# Schematic_final.net
KiCad netlist of a schematic drawn in EAGLE
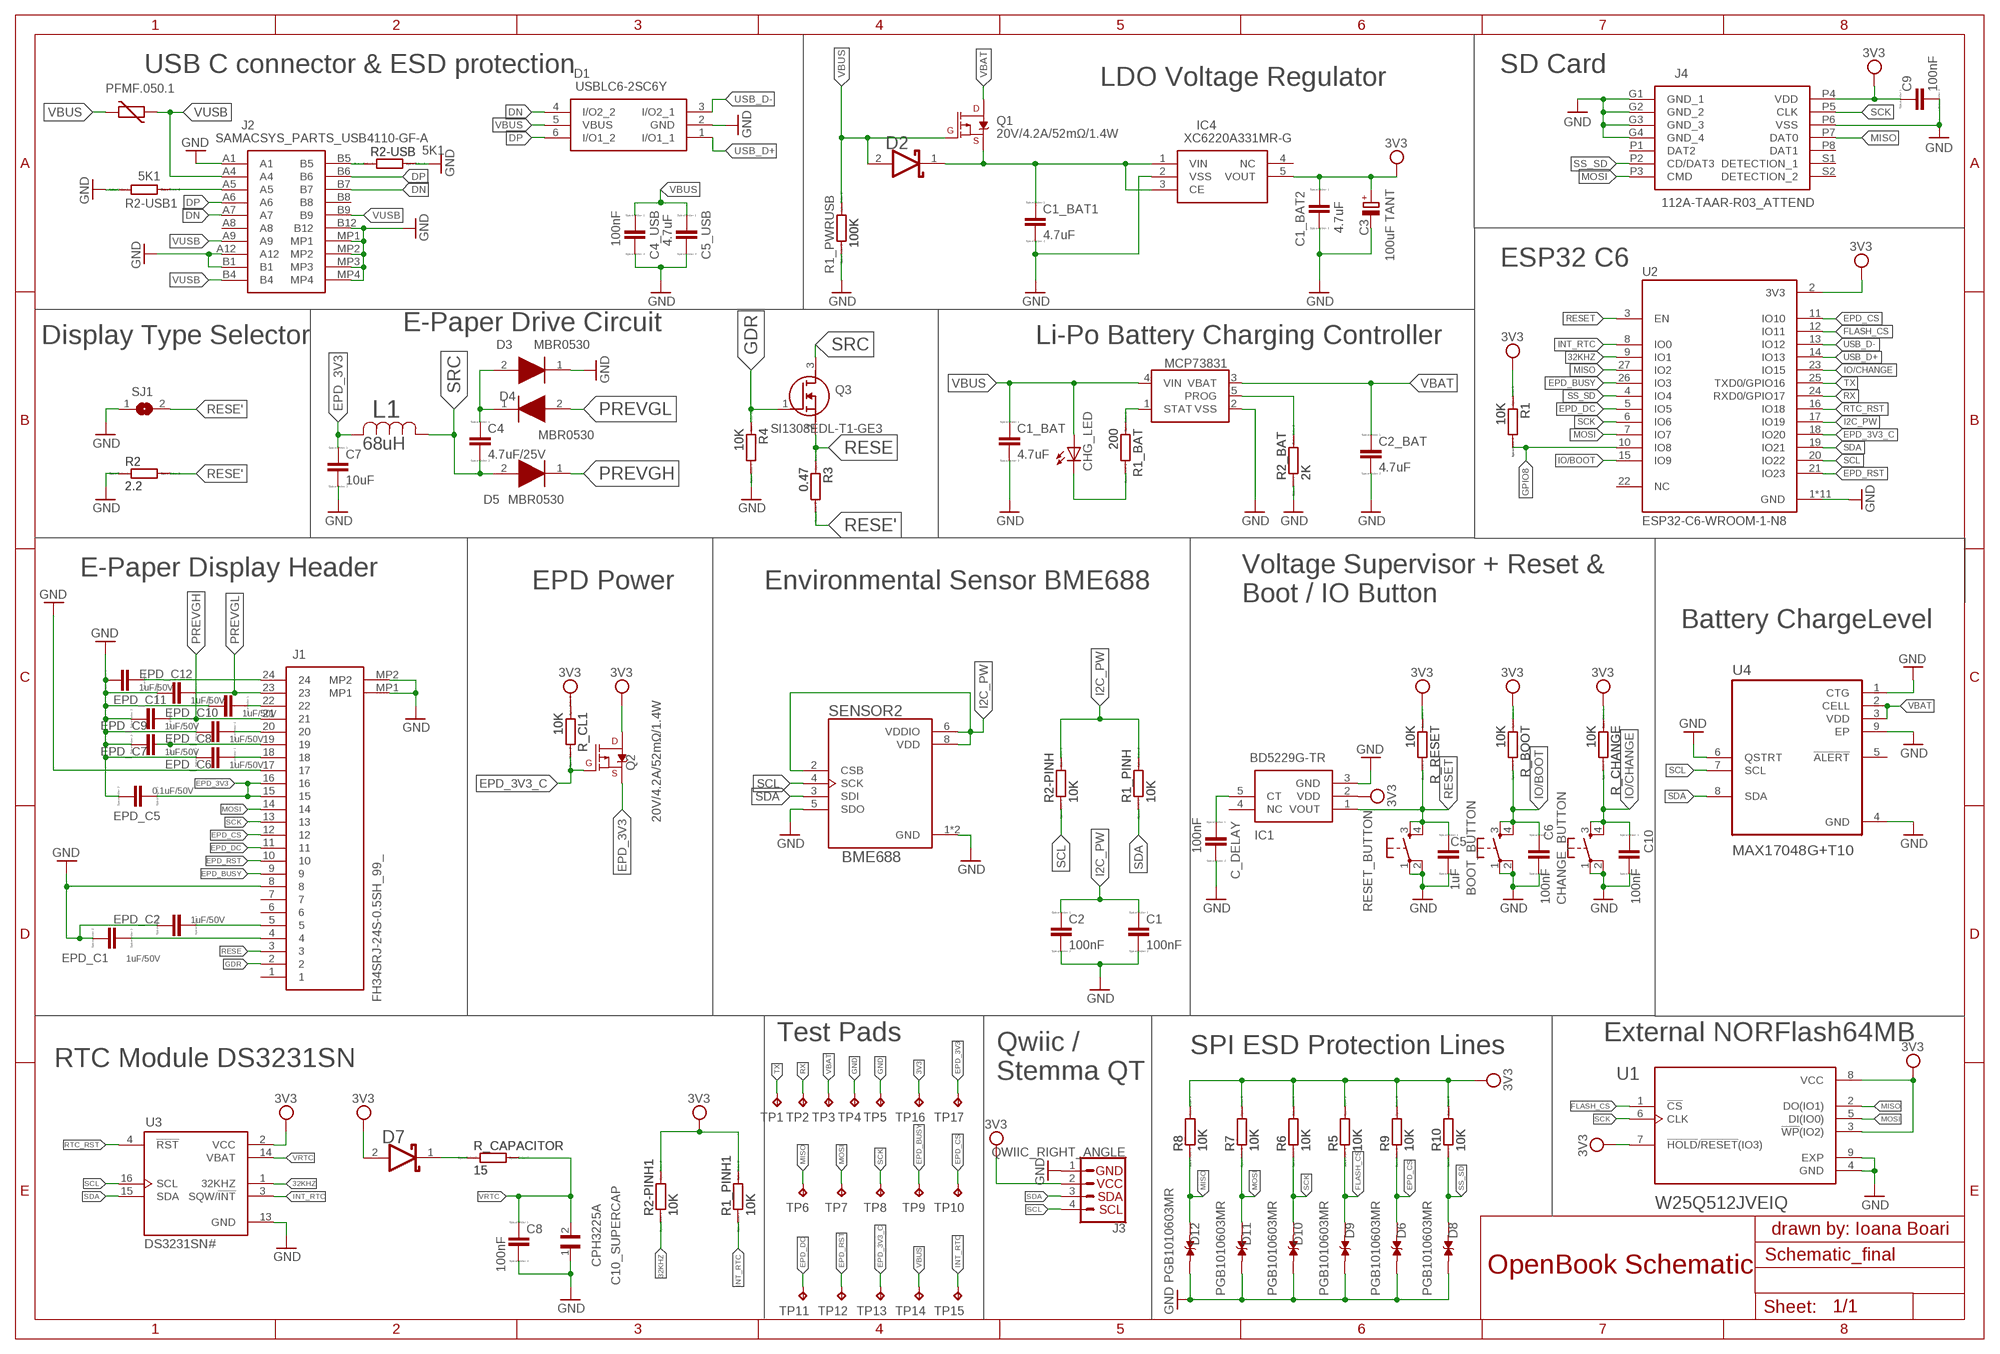
[diagram p0: schematic, sheet 1]

(export (version "E")
  (design (tool "Eeschema 10.0.6"))
  (components
    (comp (ref "BOOT_BUTTON")
      (value "BUTTON_CUSYOMV1")
      (footprint "eagle-import:MYBUTTON")
      (libsource (lib "eagle-import") (part "BUTTON_CUSYOMV1"))
    )
    (comp (ref "C1")
      (value "100nF")
      (footprint "eagle-import:ESP32_WROVER_EAGLE-LTSPICE_C0402")
      (libsource (lib "eagle-import") (part "ESP32_WROVER_EAGLE-LTSPICE_CC0402"))
    )
    (comp (ref "C1_BAT")
      (value "4.7uF")
      (footprint "eagle-import:ESP32_WROVER_EAGLE-LTSPICE_C0402")
      (libsource (lib "eagle-import") (part "ESP32_WROVER_EAGLE-LTSPICE_CC0402"))
    )
    (comp (ref "C1_BAT1")
      (value "4.7uF")
      (footprint "eagle-import:ESP32_WROVER_EAGLE-LTSPICE_C0402")
      (libsource (lib "eagle-import") (part "ESP32_WROVER_EAGLE-LTSPICE_CC0402"))
    )
    (comp (ref "C1_BAT2")
      (value "4.7uF")
      (footprint "eagle-import:EAGLE-LTSPICE_C0402")
      (libsource (lib "eagle-import") (part "EAGLE-LTSPICE_CC0402"))
    )
    (comp (ref "C2")
      (value "100nF")
      (footprint "eagle-import:ESP32_WROVER_EAGLE-LTSPICE_C0402")
      (libsource (lib "eagle-import") (part "ESP32_WROVER_EAGLE-LTSPICE_CC0402"))
    )
    (comp (ref "C2_BAT")
      (value "4.7uF")
      (footprint "eagle-import:ESP32_WROVER_EAGLE-LTSPICE_C0402")
      (libsource (lib "eagle-import") (part "ESP32_WROVER_EAGLE-LTSPICE_CC0402"))
    )
    (comp (ref "C3")
      (value "100uF TANT")
      (footprint "eagle-import:RCL_CT3528")
      (libsource (lib "eagle-import") (part "RCL_CPOL-EUCT3528"))
    )
    (comp (ref "C4")
      (value "4.7uF/25V")
      (footprint "eagle-import:ESP32_WROVER_EAGLE-LTSPICE_C0402")
      (libsource (lib "eagle-import") (part "ESP32_WROVER_EAGLE-LTSPICE_CC0402"))
    )
    (comp (ref "C4_USB")
      (value "100nF")
      (footprint "eagle-import:ESP32_WROVER_EAGLE-LTSPICE_C0402")
      (libsource (lib "eagle-import") (part "ESP32_WROVER_EAGLE-LTSPICE_CC0402"))
    )
    (comp (ref "C5")
      (value "1uF")
      (footprint "eagle-import:ESP32_WROVER_EAGLE-LTSPICE_C0402")
      (libsource (lib "eagle-import") (part "ESP32_WROVER_EAGLE-LTSPICE_CC0402"))
    )
    (comp (ref "C5_USB")
      (value "4.7uF")
      (footprint "eagle-import:ESP32_WROVER_EAGLE-LTSPICE_C0402")
      (libsource (lib "eagle-import") (part "ESP32_WROVER_EAGLE-LTSPICE_CC0402"))
    )
    (comp (ref "C6")
      (value "100nF")
      (footprint "eagle-import:ESP32_WROVER_EAGLE-LTSPICE_C0402")
      (libsource (lib "eagle-import") (part "ESP32_WROVER_EAGLE-LTSPICE_CC0402"))
    )
    (comp (ref "C7")
      (value "10uF")
      (footprint "eagle-import:ESP32_WROVER_EAGLE-LTSPICE_C0402")
      (libsource (lib "eagle-import") (part "ESP32_WROVER_EAGLE-LTSPICE_CC0402"))
    )
    (comp (ref "C8")
      (value "100nF")
      (footprint "eagle-import:ESP32_WROVER_EAGLE-LTSPICE_C0402")
      (libsource (lib "eagle-import") (part "ESP32_WROVER_EAGLE-LTSPICE_CC0402"))
    )
    (comp (ref "C9")
      (value "100nF")
      (footprint "eagle-import:ESP32_WROVER_EAGLE-LTSPICE_C0402")
      (libsource (lib "eagle-import") (part "ESP32_WROVER_EAGLE-LTSPICE_CC0402"))
    )
    (comp (ref "C10")
      (value "100nF")
      (footprint "eagle-import:ESP32_WROVER_EAGLE-LTSPICE_C0402")
      (libsource (lib "eagle-import") (part "ESP32_WROVER_EAGLE-LTSPICE_CC0402"))
    )
    (comp (ref "C10_SUPERCAP")
      (value "CPH3225A")
      (footprint "eagle-import:CAPCP3225X100N")
      (fields (field (name "MF") "Seiko Instruments"))
      (libsource (lib "eagle-import") (part "CPH3225A"))
    )
    (comp (ref "CHANGE_BUTTON")
      (value "BUTTON_CUSYOMV1")
      (footprint "eagle-import:MYBUTTON")
      (libsource (lib "eagle-import") (part "BUTTON_CUSYOMV1"))
    )
    (comp (ref "CHG_LED")
      (value "ADAFRUIT_LEDCHIP-LED0603")
      (footprint "eagle-import:ADAFRUIT_CHIP-LED0603")
      (libsource (lib "eagle-import") (part "ADAFRUIT_LEDCHIP-LED0603"))
    )
    (comp (ref "C_DELAY")
      (value "100nF")
      (footprint "eagle-import:ESP32_WROVER_EAGLE-LTSPICE_C0402")
      (libsource (lib "eagle-import") (part "ESP32_WROVER_EAGLE-LTSPICE_CC0402"))
    )
    (comp (ref "D1")
      (value "USBLC6-2SC6Y")
      (footprint "eagle-import:SOT95P280X145-6N")
      (fields (field (name "MF") "STMicroelectronics"))
      (libsource (lib "eagle-import") (part "USBLC6-2SC6Y"))
    )
    (comp (ref "D2")
      (value "ESP32_WROVER_AVX---SD0805S020S1R0_AVX_SD0805S020S1R0_0_0AVX_SD0805S020S1R0_0_0")
      (footprint "eagle-import:ESP32_WROVER_AVX---SD0805S020S1R0_AVX_SD0805S020S1R0_0")
      (fields
        (field (name "DIGIKEY_PART_NUMBER") "478-7800-1-ND")
        (field (name "MF") "AVX")
        (field (name "MOUSER_PART_NUMBER") "581-SD0805S020S1R0")
      )
      (libsource (lib "eagle-import") (part "ESP32_WROVER_AVX---SD0805S020S1R0_AVX_SD0805S020S1R0_0_0AVX_SD0805S020S1R0_0_0"))
    )
    (comp (ref "D3")
      (value "MBR0530")
      (footprint "eagle-import:SOD3716X135N")
      (fields (field (name "MF") "ON Semiconductor"))
      (libsource (lib "eagle-import") (part "MBR0530"))
    )
    (comp (ref "D4")
      (value "MBR0530")
      (footprint "eagle-import:SOD3716X135N")
      (fields (field (name "MF") "ON Semiconductor"))
      (libsource (lib "eagle-import") (part "MBR0530"))
    )
    (comp (ref "D5")
      (value "MBR0530")
      (footprint "eagle-import:SOD3716X135N")
      (fields (field (name "MF") "ON Semiconductor"))
      (libsource (lib "eagle-import") (part "MBR0530"))
    )
    (comp (ref "D6")
      (value "PGB1010603MR")
      (footprint "eagle-import:DIOC1608X36N")
      (fields (field (name "MF") "Littelfuse Inc."))
      (libsource (lib "eagle-import") (part "PGB1010603MR"))
    )
    (comp (ref "D7")
      (value "ESP32_WROVER_AVX---SD0805S020S1R0_AVX_SD0805S020S1R0_0_0AVX_SD0805S020S1R0_0_0")
      (footprint "eagle-import:ESP32_WROVER_AVX---SD0805S020S1R0_AVX_SD0805S020S1R0_0")
      (fields
        (field (name "DIGIKEY_PART_NUMBER") "478-7800-1-ND")
        (field (name "MF") "AVX")
        (field (name "MOUSER_PART_NUMBER") "581-SD0805S020S1R0")
      )
      (libsource (lib "eagle-import") (part "ESP32_WROVER_AVX---SD0805S020S1R0_AVX_SD0805S020S1R0_0_0AVX_SD0805S020S1R0_0_0"))
    )
    (comp (ref "D8")
      (value "PGB1010603MR")
      (footprint "eagle-import:DIOC1608X36N")
      (fields (field (name "MF") "Littelfuse Inc."))
      (libsource (lib "eagle-import") (part "PGB1010603MR"))
    )
    (comp (ref "D9")
      (value "PGB1010603MR")
      (footprint "eagle-import:DIOC1608X36N")
      (fields (field (name "MF") "Littelfuse Inc."))
      (libsource (lib "eagle-import") (part "PGB1010603MR"))
    )
    (comp (ref "D10")
      (value "PGB1010603MR")
      (footprint "eagle-import:DIOC1608X36N")
      (fields (field (name "MF") "Littelfuse Inc."))
      (libsource (lib "eagle-import") (part "PGB1010603MR"))
    )
    (comp (ref "D11")
      (value "PGB1010603MR")
      (footprint "eagle-import:DIOC1608X36N")
      (fields (field (name "MF") "Littelfuse Inc."))
      (libsource (lib "eagle-import") (part "PGB1010603MR"))
    )
    (comp (ref "D12")
      (value "PGB1010603MR")
      (footprint "eagle-import:DIOC1608X36N")
      (fields (field (name "MF") "Littelfuse Inc."))
      (libsource (lib "eagle-import") (part "PGB1010603MR"))
    )
    (comp (ref "EPD_C1")
      (value "1uF/50V")
      (footprint "eagle-import:ESP32_WROVER_EAGLE-LTSPICE_C0402")
      (libsource (lib "eagle-import") (part "ESP32_WROVER_EAGLE-LTSPICE_CC0402"))
    )
    (comp (ref "EPD_C2")
      (value "1uF/50V")
      (footprint "eagle-import:ESP32_WROVER_EAGLE-LTSPICE_C0402")
      (libsource (lib "eagle-import") (part "ESP32_WROVER_EAGLE-LTSPICE_CC0402"))
    )
    (comp (ref "EPD_C5")
      (value "0.1uF/50V")
      (footprint "eagle-import:ESP32_WROVER_EAGLE-LTSPICE_C0402")
      (libsource (lib "eagle-import") (part "ESP32_WROVER_EAGLE-LTSPICE_CC0402"))
    )
    (comp (ref "EPD_C6")
      (value "1uF/50V")
      (footprint "eagle-import:ESP32_WROVER_EAGLE-LTSPICE_C0402")
      (libsource (lib "eagle-import") (part "ESP32_WROVER_EAGLE-LTSPICE_CC0402"))
    )
    (comp (ref "EPD_C7")
      (value "1uF/50V")
      (footprint "eagle-import:ESP32_WROVER_EAGLE-LTSPICE_C0402")
      (libsource (lib "eagle-import") (part "ESP32_WROVER_EAGLE-LTSPICE_CC0402"))
    )
    (comp (ref "EPD_C8")
      (value "1uF/50V")
      (footprint "eagle-import:ESP32_WROVER_EAGLE-LTSPICE_C0402")
      (libsource (lib "eagle-import") (part "ESP32_WROVER_EAGLE-LTSPICE_CC0402"))
    )
    (comp (ref "EPD_C9")
      (value "1uF/50V")
      (footprint "eagle-import:ESP32_WROVER_EAGLE-LTSPICE_C0402")
      (libsource (lib "eagle-import") (part "ESP32_WROVER_EAGLE-LTSPICE_CC0402"))
    )
    (comp (ref "EPD_C10")
      (value "1uF/50V")
      (footprint "eagle-import:ESP32_WROVER_EAGLE-LTSPICE_C0402")
      (libsource (lib "eagle-import") (part "ESP32_WROVER_EAGLE-LTSPICE_CC0402"))
    )
    (comp (ref "EPD_C11")
      (value "1uF/50V")
      (footprint "eagle-import:ESP32_WROVER_EAGLE-LTSPICE_C0402")
      (libsource (lib "eagle-import") (part "ESP32_WROVER_EAGLE-LTSPICE_CC0402"))
    )
    (comp (ref "EPD_C12")
      (value "1uF/50V")
      (footprint "eagle-import:ESP32_WROVER_EAGLE-LTSPICE_C0402")
      (libsource (lib "eagle-import") (part "ESP32_WROVER_EAGLE-LTSPICE_CC0402"))
    )
    (comp (ref "IC1")
      (value "BD5229G-TR")
      (footprint "eagle-import:SOT95P280X125-5N")
      (fields (field (name "MOUSER_PART_NUMBER") "755-BD5229G-TR"))
      (libsource (lib "eagle-import") (part "BD5229G-TR"))
    )
    (comp (ref "IC4")
      (value "XC6220A331MR-G")
      (footprint "eagle-import:SOT95P280X120-5N")
      (fields (field (name "MOUSER_PART_NUMBER") "865-XC6220A331MR-G"))
      (libsource (lib "eagle-import") (part "XC6220A331MR-G"))
    )
    (comp (ref "J1")
      (value "FH34SRJ-24S-0.5SH_99_")
      (footprint "eagle-import:FH34SRJ24S05SH99")
      (fields
        (field (name "MANUFACTURER_PART_NUMBER") "FH34SRJ-24S-0.5SH(99)")
        (field (name "MOUSER_PART_NUMBER") "798-FH34SRJ24S05SH99")
      )
      (libsource (lib "eagle-import") (part "FH34SRJ-24S-0.5SH_99_"))
    )
    (comp (ref "J2")
      (value "SAMACSYS_PARTS_USB4110-GF-A")
      (footprint "eagle-import:SAMACSYS_PARTS_USB4110GFA")
      (fields
        (field (name "MANUFACTURER_PART_NUMBER") "USB4110-GF-A")
        (field (name "MOUSER_PART_NUMBER") "640-USB4110-GF-A")
      )
      (libsource (lib "eagle-import") (part "SAMACSYS_PARTS_USB4110-GF-A"))
    )
    (comp (ref "J3")
      (value "QWIIC_RIGHT_ANGLE")
      (footprint "eagle-import:JST04_1MM_RA")
      (libsource (lib "eagle-import") (part "QWIIC_CONNECTORJS-1MM"))
    )
    (comp (ref "J4")
      (value "112A-TAAR-R03_ATTEND")
      (footprint "eagle-import:112ATAARR03ATTEND")
      (fields (field (name "MANUFACTURER_PART_NUMBER") "112A-TAAR-R03 ATTEND"))
      (libsource (lib "eagle-import") (part "112A-TAAR-R03_ATTEND"))
    )
    (comp (ref "L1")
      (value "68uH")
      (footprint "eagle-import:IND_4828-WE-TPC_WRE")
      (fields
        (field (name "MANUFACTURER_PART_NUMBER") "744043680")
        (field (name "COPYRIGHT") "Copyright (C) 2024 Ultra Librarian. All rights reserved.")
      )
      (libsource (lib "eagle-import") (part "744043680IND_4828-WE-TPC_WRE"))
    )
    (comp (ref "MCP73831")
      (value "MCP73831")
      (footprint "eagle-import:ESP32_WROVER_SPARKFUN-IC-POWER_SOT23-5")
      (libsource (lib "eagle-import") (part "ESP32_WROVER_SPARKFUN-IC-POWER_MCP73831"))
    )
    (comp (ref "PFMF.050.1")
      (value "ESP32C6_VARISTORCN1812")
      (footprint "eagle-import:ESP32C6_VARISTOR_CT_CN1812")
      (libsource (lib "eagle-import") (part "ESP32C6_VARISTORCN1812"))
    )
    (comp (ref "Q1")
      (value "20V/4.2A/52mΩ/1.4W")
      (footprint "eagle-import:ESP32_WROVER_SPARKFUN-DISCRETESEMI_SOT23-3")
      (libsource (lib "eagle-import") (part "ESP32_WROVER_SPARKFUN-DISCRETESEMI_MOSFET_PCH-DMG2305UX-7"))
    )
    (comp (ref "Q2")
      (value "20V/4.2A/52mΩ/1.4W")
      (footprint "eagle-import:ESP32_WROVER_SPARKFUN-DISCRETESEMI_SOT23-3")
      (libsource (lib "eagle-import") (part "ESP32_WROVER_SPARKFUN-DISCRETESEMI_MOSFET_PCH-DMG2305UX-7"))
    )
    (comp (ref "Q3")
      (value "SI1308EDL-T1-GE3")
      (footprint "eagle-import:SOT65P210X110-3N")
      (fields (field (name "MF") "Vishay Siliconix"))
      (libsource (lib "eagle-import") (part "SI1308EDL-T1-GE3"))
    )
    (comp (ref "R1")
      (value "10K")
      (footprint "eagle-import:ESP32_WROVER_EAGLE-LTSPICE_R0402")
      (libsource (lib "eagle-import") (part "ESP32_WROVER_EAGLE-LTSPICE_RR0402"))
    )
    (comp (ref "R1_BAT")
      (value "200")
      (footprint "eagle-import:ESP32_WROVER_EAGLE-LTSPICE_R0402")
      (libsource (lib "eagle-import") (part "ESP32_WROVER_EAGLE-LTSPICE_RR0402"))
    )
    (comp (ref "R1_PINH")
      (value "10K")
      (footprint "eagle-import:ESP32_WROVER_EAGLE-LTSPICE_R0402")
      (libsource (lib "eagle-import") (part "ESP32_WROVER_EAGLE-LTSPICE_RR0402"))
    )
    (comp (ref "R1_PINH1")
      (value "10K")
      (footprint "eagle-import:ESP32_WROVER_EAGLE-LTSPICE_R0402")
      (libsource (lib "eagle-import") (part "ESP32_WROVER_EAGLE-LTSPICE_RR0402"))
    )
    (comp (ref "R1_PWRUSB")
      (value "100K")
      (footprint "eagle-import:ESP32_WROVER_EAGLE-LTSPICE_R0402")
      (libsource (lib "eagle-import") (part "ESP32_WROVER_EAGLE-LTSPICE_RR0402"))
    )
    (comp (ref "R2")
      (value "2.2")
      (footprint "eagle-import:ESP32_WROVER_EAGLE-LTSPICE_R0402")
      (libsource (lib "eagle-import") (part "ESP32_WROVER_EAGLE-LTSPICE_RR0402"))
    )
    (comp (ref "R2-PINH")
      (value "10K")
      (footprint "eagle-import:ESP32_WROVER_EAGLE-LTSPICE_R0402")
      (libsource (lib "eagle-import") (part "ESP32_WROVER_EAGLE-LTSPICE_RR0402"))
    )
    (comp (ref "R2-PINH1")
      (value "10K")
      (footprint "eagle-import:ESP32_WROVER_EAGLE-LTSPICE_R0402")
      (libsource (lib "eagle-import") (part "ESP32_WROVER_EAGLE-LTSPICE_RR0402"))
    )
    (comp (ref "R2-USB")
      (value "5K1")
      (footprint "eagle-import:ESP32_WROVER_EAGLE-LTSPICE_R0402")
      (libsource (lib "eagle-import") (part "ESP32_WROVER_EAGLE-LTSPICE_RR0402"))
    )
    (comp (ref "R2-USB1")
      (value "5K1")
      (footprint "eagle-import:ESP32_WROVER_EAGLE-LTSPICE_R0402")
      (libsource (lib "eagle-import") (part "ESP32_WROVER_EAGLE-LTSPICE_RR0402"))
    )
    (comp (ref "R2_BAT")
      (value "2K")
      (footprint "eagle-import:ESP32_WROVER_EAGLE-LTSPICE_R0402")
      (libsource (lib "eagle-import") (part "ESP32_WROVER_EAGLE-LTSPICE_RR0402"))
    )
    (comp (ref "R3")
      (value "0.47")
      (footprint "eagle-import:ESP32_WROVER_EAGLE-LTSPICE_R0402")
      (libsource (lib "eagle-import") (part "ESP32_WROVER_EAGLE-LTSPICE_RR0402"))
    )
    (comp (ref "R4")
      (value "10K")
      (footprint "eagle-import:ESP32_WROVER_EAGLE-LTSPICE_R0402")
      (libsource (lib "eagle-import") (part "ESP32_WROVER_EAGLE-LTSPICE_RR0402"))
    )
    (comp (ref "R5")
      (value "10K")
      (footprint "eagle-import:ESP32_WROVER_EAGLE-LTSPICE_R0402")
      (libsource (lib "eagle-import") (part "ESP32_WROVER_EAGLE-LTSPICE_RR0402"))
    )
    (comp (ref "R6")
      (value "10K")
      (footprint "eagle-import:ESP32_WROVER_EAGLE-LTSPICE_R0402")
      (libsource (lib "eagle-import") (part "ESP32_WROVER_EAGLE-LTSPICE_RR0402"))
    )
    (comp (ref "R7")
      (value "10K")
      (footprint "eagle-import:ESP32_WROVER_EAGLE-LTSPICE_R0402")
      (libsource (lib "eagle-import") (part "ESP32_WROVER_EAGLE-LTSPICE_RR0402"))
    )
    (comp (ref "R8")
      (value "10K")
      (footprint "eagle-import:ESP32_WROVER_EAGLE-LTSPICE_R0402")
      (libsource (lib "eagle-import") (part "ESP32_WROVER_EAGLE-LTSPICE_RR0402"))
    )
    (comp (ref "R9")
      (value "10K")
      (footprint "eagle-import:ESP32_WROVER_EAGLE-LTSPICE_R0402")
      (libsource (lib "eagle-import") (part "ESP32_WROVER_EAGLE-LTSPICE_RR0402"))
    )
    (comp (ref "R10")
      (value "10K")
      (footprint "eagle-import:ESP32_WROVER_EAGLE-LTSPICE_R0402")
      (libsource (lib "eagle-import") (part "ESP32_WROVER_EAGLE-LTSPICE_RR0402"))
    )
    (comp (ref "RESET_BUTTON")
      (value "BUTTON_CUSYOMV1")
      (footprint "eagle-import:MYBUTTON")
      (libsource (lib "eagle-import") (part "BUTTON_CUSYOMV1"))
    )
    (comp (ref "R_BOOT")
      (value "10K")
      (footprint "eagle-import:ESP32_WROVER_EAGLE-LTSPICE_R0402")
      (libsource (lib "eagle-import") (part "ESP32_WROVER_EAGLE-LTSPICE_RR0402"))
    )
    (comp (ref "R_CAPACITOR")
      (value "15")
      (footprint "eagle-import:ESP32_WROVER_EAGLE-LTSPICE_R0402")
      (libsource (lib "eagle-import") (part "ESP32_WROVER_EAGLE-LTSPICE_RR0402"))
    )
    (comp (ref "R_CHANGE")
      (value "10K")
      (footprint "eagle-import:ESP32_WROVER_EAGLE-LTSPICE_R0402")
      (libsource (lib "eagle-import") (part "ESP32_WROVER_EAGLE-LTSPICE_RR0402"))
    )
    (comp (ref "R_CL1")
      (value "10K")
      (footprint "eagle-import:ESP32_WROVER_EAGLE-LTSPICE_R0402")
      (libsource (lib "eagle-import") (part "ESP32_WROVER_EAGLE-LTSPICE_RR0402"))
    )
    (comp (ref "R_RESET")
      (value "10K")
      (footprint "eagle-import:ESP32_WROVER_EAGLE-LTSPICE_R0402")
      (libsource (lib "eagle-import") (part "ESP32_WROVER_EAGLE-LTSPICE_RR0402"))
    )
    (comp (ref "SENSOR2")
      (value "BME688")
      (footprint "eagle-import:ESP32_WROVER_BME680_PSON80P300X300X100-8N")
      (fields (field (name "MF") "Bosch Sensortec") (field (name "MP") "BME680"))
      (libsource (lib "eagle-import") (part "ESP32_WROVER_BME680_BME680"))
    )
    (comp (ref "SJ1") (value "SJ") (footprint "eagle-import:SJ") (libsource (lib "eagle-import") (part "SJ")))
    (comp (ref "TP1")
      (value "TPTP20R")
      (footprint "eagle-import:TP20R")
      (libsource (lib "eagle-import") (part "TPTP20R"))
    )
    (comp (ref "TP2")
      (value "TPTP20R")
      (footprint "eagle-import:TP20R")
      (libsource (lib "eagle-import") (part "TPTP20R"))
    )
    (comp (ref "TP3")
      (value "TPTP20R")
      (footprint "eagle-import:TP20R")
      (libsource (lib "eagle-import") (part "TPTP20R"))
    )
    (comp (ref "TP4")
      (value "TPTP20R")
      (footprint "eagle-import:TP20R")
      (libsource (lib "eagle-import") (part "TPTP20R"))
    )
    (comp (ref "TP5")
      (value "TPTP20R")
      (footprint "eagle-import:TP20R")
      (libsource (lib "eagle-import") (part "TPTP20R"))
    )
    (comp (ref "TP6")
      (value "TPTP20R")
      (footprint "eagle-import:TP20R")
      (libsource (lib "eagle-import") (part "TPTP20R"))
    )
    (comp (ref "TP7")
      (value "TPTP20R")
      (footprint "eagle-import:TP20R")
      (libsource (lib "eagle-import") (part "TPTP20R"))
    )
    (comp (ref "TP8")
      (value "TPTP20R")
      (footprint "eagle-import:TP20R")
      (libsource (lib "eagle-import") (part "TPTP20R"))
    )
    (comp (ref "TP9")
      (value "TPTP20R")
      (footprint "eagle-import:TP20R")
      (libsource (lib "eagle-import") (part "TPTP20R"))
    )
    (comp (ref "TP10")
      (value "TPTP20R")
      (footprint "eagle-import:TP20R")
      (libsource (lib "eagle-import") (part "TPTP20R"))
    )
    (comp (ref "TP11")
      (value "TPTP20R")
      (footprint "eagle-import:TP20R")
      (libsource (lib "eagle-import") (part "TPTP20R"))
    )
    (comp (ref "TP12")
      (value "TPTP20R")
      (footprint "eagle-import:TP20R")
      (libsource (lib "eagle-import") (part "TPTP20R"))
    )
    (comp (ref "TP13")
      (value "TPTP20R")
      (footprint "eagle-import:TP20R")
      (libsource (lib "eagle-import") (part "TPTP20R"))
    )
    (comp (ref "TP14")
      (value "TPTP20R")
      (footprint "eagle-import:TP20R")
      (libsource (lib "eagle-import") (part "TPTP20R"))
    )
    (comp (ref "TP15")
      (value "TPTP20R")
      (footprint "eagle-import:TP20R")
      (libsource (lib "eagle-import") (part "TPTP20R"))
    )
    (comp (ref "TP16")
      (value "TPTP20R")
      (footprint "eagle-import:TP20R")
      (libsource (lib "eagle-import") (part "TPTP20R"))
    )
    (comp (ref "TP17")
      (value "TPTP20R")
      (footprint "eagle-import:TP20R")
      (libsource (lib "eagle-import") (part "TPTP20R"))
    )
    (comp (ref "U1")
      (value "W25Q512JVEIQ")
      (footprint "eagle-import:SON127P600X800X80-9N")
      (fields (field (name "MF") "Winbond Electronics"))
      (libsource (lib "eagle-import") (part "W25Q512JVEIQ"))
    )
    (comp (ref "U2")
      (value "ESP32-C6-WROOM-1-N8")
      (footprint "eagle-import:XCVR_ESP32-C6-WROOM-1-N8")
      (fields (field (name "MF") "Espressif Systems"))
      (libsource (lib "eagle-import") (part "ESP32-C6-WROOM-1-N8"))
    )
    (comp (ref "U3")
      (value "DS3231SN#")
      (footprint "eagle-import:SOIC127P1032X265-16N")
      (fields (field (name "MF") "Analog Devices"))
      (libsource (lib "eagle-import") (part "DS3231SN#"))
    )
    (comp (ref "U4")
      (value "MAX17048G+T10")
      (footprint "eagle-import:SON50P200X200X80-9N")
      (fields (field (name "MF") "Analog Devices"))
      (libsource (lib "eagle-import") (part "MAX17048G+T10"))
    )
  )
  (nets
    (net (code "1") (name "3V3") (class "Default")
      (node (ref "C1_BAT2") (pin "1") (pinfunction "1_1") (pintype "passive"))
      (node (ref "C3") (pin "+") (pinfunction "+_+") (pintype "passive"))
      (node (ref "C9") (pin "1") (pinfunction "1_1") (pintype "passive"))
      (node (ref "D7") (pin "2") (pinfunction "ANODE_2") (pintype "bidirectional"))
      (node (ref "IC1") (pin "2") (pinfunction "VDD_2") (pintype "bidirectional"))
      (node (ref "IC4") (pin "5") (pinfunction "VOUT_5") (pintype "bidirectional"))
      (node (ref "J3") (pin "2") (pinfunction "2_2") (pintype "power_in"))
      (node (ref "J4") (pin "P4") (pinfunction "VDD_P4") (pintype "bidirectional"))
      (node (ref "Q2") (pin "3") (pinfunction "D_3") (pintype "bidirectional"))
      (node (ref "R1") (pin "1") (pinfunction "1_1") (pintype "passive"))
      (node (ref "R10") (pin "2") (pinfunction "2_2") (pintype "passive"))
      (node (ref "R1_PINH1") (pin "2") (pinfunction "2_2") (pintype "passive"))
      (node (ref "R2-PINH1") (pin "2") (pinfunction "2_2") (pintype "passive"))
      (node (ref "R5") (pin "2") (pinfunction "2_2") (pintype "passive"))
      (node (ref "R6") (pin "2") (pinfunction "2_2") (pintype "passive"))
      (node (ref "R7") (pin "2") (pinfunction "2_2") (pintype "passive"))
      (node (ref "R8") (pin "2") (pinfunction "2_2") (pintype "passive"))
      (node (ref "R9") (pin "2") (pinfunction "2_2") (pintype "passive"))
      (node (ref "R_BOOT") (pin "1") (pinfunction "1_1") (pintype "passive"))
      (node (ref "R_CHANGE") (pin "1") (pinfunction "1_1") (pintype "passive"))
      (node (ref "R_CL1") (pin "1") (pinfunction "1_1") (pintype "passive"))
      (node (ref "R_RESET") (pin "1") (pinfunction "1_1") (pintype "passive"))
      (node (ref "TP16") (pin "TP") (pinfunction "TP_TP") (pintype "input"))
      (node (ref "U1") (pin "3") (pinfunction "~{WP}(IO2)_3") (pintype "bidirectional"))
      (node (ref "U1") (pin "7") (pinfunction "~{HOLD}/~{RESET}(IO3)_7") (pintype "bidirectional"))
      (node (ref "U1") (pin "8") (pinfunction "VCC_8") (pintype "power_in"))
      (node (ref "U2") (pin "2") (pinfunction "3V3_2") (pintype "power_in"))
      (node (ref "U3") (pin "2") (pinfunction "VCC_2") (pintype "power_in"))
    )
    (net (code "2") (name "32KHZ") (class "Default")
      (node (ref "R2-PINH1") (pin "1") (pinfunction "1_1") (pintype "passive"))
      (node (ref "U2") (pin "9") (pinfunction "IO1_9") (pintype "bidirectional"))
      (node (ref "U3") (pin "1") (pinfunction "32KHZ_1") (pintype "output"))
    )
    (net (code "3") (name "DN") (class "Default")
      (node (ref "D1") (pin "4") (pinfunction "I/O2_2_4") (pintype "bidirectional"))
      (node (ref "J2") (pin "A7") (pinfunction "A7_A7") (pintype "bidirectional"))
      (node (ref "J2") (pin "B7") (pinfunction "B7_B7") (pintype "bidirectional"))
    )
    (net (code "4") (name "DP") (class "Default")
      (node (ref "D1") (pin "6") (pinfunction "I/O1_2_6") (pintype "bidirectional"))
      (node (ref "J2") (pin "A6") (pinfunction "A6_A6") (pintype "bidirectional"))
      (node (ref "J2") (pin "B6") (pinfunction "B6_B6") (pintype "bidirectional"))
    )
    (net (code "5") (name "EPD_3V3") (class "Default")
      (node (ref "C7") (pin "1") (pinfunction "1_1") (pintype "passive"))
      (node (ref "EPD_C5") (pin "1") (pinfunction "1_1") (pintype "passive"))
      (node (ref "J1") (pin "15") (pinfunction "15_15") (pintype "bidirectional"))
      (node (ref "J1") (pin "16") (pinfunction "16_16") (pintype "bidirectional"))
      (node (ref "L1") (pin "2") (pinfunction "2_2") (pintype "passive"))
      (node (ref "Q2") (pin "2") (pinfunction "S_2") (pintype "bidirectional"))
      (node (ref "TP17") (pin "TP") (pinfunction "TP_TP") (pintype "input"))
    )
    (net (code "6") (name "EPD_3V3_C") (class "Default")
      (node (ref "Q2") (pin "1") (pinfunction "G_1") (pintype "bidirectional"))
      (node (ref "R_CL1") (pin "2") (pinfunction "2_2") (pintype "passive"))
      (node (ref "TP13") (pin "TP") (pinfunction "TP_TP") (pintype "input"))
      (node (ref "U2") (pin "18") (pinfunction "IO20_18") (pintype "bidirectional"))
    )
    (net (code "7") (name "EPD_BUSY") (class "Default")
      (node (ref "J1") (pin "9") (pinfunction "9_9") (pintype "bidirectional"))
      (node (ref "TP9") (pin "TP") (pinfunction "TP_TP") (pintype "input"))
      (node (ref "U2") (pin "26") (pinfunction "IO3_26") (pintype "bidirectional"))
    )
    (net (code "8") (name "EPD_CS") (class "Default")
      (node (ref "D6") (pin "1") (pinfunction "1_1") (pintype "passive"))
      (node (ref "J1") (pin "12") (pinfunction "12_12") (pintype "bidirectional"))
      (node (ref "R9") (pin "1") (pinfunction "1_1") (pintype "passive"))
      (node (ref "TP10") (pin "TP") (pinfunction "TP_TP") (pintype "input"))
      (node (ref "U2") (pin "11") (pinfunction "IO10_11") (pintype "bidirectional"))
    )
    (net (code "9") (name "EPD_DC") (class "Default")
      (node (ref "J1") (pin "11") (pinfunction "11_11") (pintype "bidirectional"))
      (node (ref "TP11") (pin "TP") (pinfunction "TP_TP") (pintype "input"))
      (node (ref "U2") (pin "5") (pinfunction "IO5_5") (pintype "bidirectional"))
    )
    (net (code "10") (name "EPD_RST") (class "Default")
      (node (ref "J1") (pin "10") (pinfunction "10_10") (pintype "bidirectional"))
      (node (ref "TP12") (pin "TP") (pinfunction "TP_TP") (pintype "input"))
      (node (ref "U2") (pin "21") (pinfunction "IO23_21") (pintype "bidirectional"))
    )
    (net (code "11") (name "FLASH_CS") (class "Default")
      (node (ref "D9") (pin "1") (pinfunction "1_1") (pintype "passive"))
      (node (ref "R5") (pin "1") (pinfunction "1_1") (pintype "passive"))
      (node (ref "U1") (pin "1") (pinfunction "~{CS}_1") (pintype "input"))
      (node (ref "U2") (pin "12") (pinfunction "IO11_12") (pintype "bidirectional"))
    )
    (net (code "12") (name "GDR") (class "Default")
      (node (ref "J1") (pin "2") (pinfunction "2_2") (pintype "bidirectional"))
      (node (ref "Q3") (pin "1") (pinfunction "G_1") (pintype "bidirectional"))
      (node (ref "R4") (pin "1") (pinfunction "1_1") (pintype "passive"))
    )
    (net (code "13") (name "GND") (class "Default")
      (node (ref "BOOT_BUTTON") (pin "1") (pinfunction "1_1") (pintype "passive"))
      (node (ref "BOOT_BUTTON") (pin "2") (pinfunction "2_2") (pintype "passive"))
      (node (ref "C1") (pin "2") (pinfunction "2_2") (pintype "passive"))
      (node (ref "C10") (pin "2") (pinfunction "2_2") (pintype "passive"))
      (node (ref "C10_SUPERCAP") (pin "1") (pinfunction "1_1") (pintype "passive"))
      (node (ref "C1_BAT") (pin "2") (pinfunction "2_2") (pintype "passive"))
      (node (ref "C1_BAT1") (pin "2") (pinfunction "2_2") (pintype "passive"))
      (node (ref "C1_BAT2") (pin "2") (pinfunction "2_2") (pintype "passive"))
      (node (ref "C2") (pin "2") (pinfunction "2_2") (pintype "passive"))
      (node (ref "C2_BAT") (pin "2") (pinfunction "2_2") (pintype "passive"))
      (node (ref "C3") (pin "-") (pinfunction "-_-") (pintype "passive"))
      (node (ref "C4_USB") (pin "2") (pinfunction "2_2") (pintype "passive"))
      (node (ref "C5") (pin "2") (pinfunction "2_2") (pintype "passive"))
      (node (ref "C5_USB") (pin "2") (pinfunction "2_2") (pintype "passive"))
      (node (ref "C6") (pin "2") (pinfunction "2_2") (pintype "passive"))
      (node (ref "C7") (pin "2") (pinfunction "2_2") (pintype "passive"))
      (node (ref "C8") (pin "2") (pinfunction "2_2") (pintype "passive"))
      (node (ref "C9") (pin "2") (pinfunction "2_2") (pintype "passive"))
      (node (ref "CHANGE_BUTTON") (pin "1") (pinfunction "1_1") (pintype "passive"))
      (node (ref "CHANGE_BUTTON") (pin "2") (pinfunction "2_2") (pintype "passive"))
      (node (ref "C_DELAY") (pin "2") (pinfunction "2_2") (pintype "passive"))
      (node (ref "D1") (pin "2") (pinfunction "GND_2") (pintype "bidirectional"))
      (node (ref "D10") (pin "2") (pinfunction "2_2") (pintype "passive"))
      (node (ref "D11") (pin "2") (pinfunction "2_2") (pintype "passive"))
      (node (ref "D12") (pin "2") (pinfunction "2_2") (pintype "passive"))
      (node (ref "D3") (pin "1") (pinfunction "K_1") (pintype "bidirectional"))
      (node (ref "D6") (pin "2") (pinfunction "2_2") (pintype "passive"))
      (node (ref "D8") (pin "2") (pinfunction "2_2") (pintype "passive"))
      (node (ref "D9") (pin "2") (pinfunction "2_2") (pintype "passive"))
      (node (ref "EPD_C1") (pin "2") (pinfunction "2_2") (pintype "passive"))
      (node (ref "EPD_C10") (pin "2") (pinfunction "2_2") (pintype "passive"))
      (node (ref "EPD_C11") (pin "2") (pinfunction "2_2") (pintype "passive"))
      (node (ref "EPD_C12") (pin "2") (pinfunction "2_2") (pintype "passive"))
      (node (ref "EPD_C2") (pin "2") (pinfunction "2_2") (pintype "passive"))
      (node (ref "EPD_C5") (pin "2") (pinfunction "2_2") (pintype "passive"))
      (node (ref "EPD_C6") (pin "2") (pinfunction "2_2") (pintype "passive"))
      (node (ref "EPD_C7") (pin "2") (pinfunction "2_2") (pintype "passive"))
      (node (ref "EPD_C8") (pin "2") (pinfunction "2_2") (pintype "passive"))
      (node (ref "EPD_C9") (pin "2") (pinfunction "2_2") (pintype "passive"))
      (node (ref "IC1") (pin "3") (pinfunction "GND_3") (pintype "bidirectional"))
      (node (ref "IC4") (pin "2") (pinfunction "VSS_2") (pintype "bidirectional"))
      (node (ref "J1") (pin "17") (pinfunction "17_17") (pintype "bidirectional"))
      (node (ref "J1") (pin "8") (pinfunction "8_8") (pintype "bidirectional"))
      (node (ref "J1") (pin "MP1") (pinfunction "MP1_MP1") (pintype "bidirectional"))
      (node (ref "J1") (pin "MP2") (pinfunction "MP2_MP2") (pintype "bidirectional"))
      (node (ref "J2") (pin "A1") (pinfunction "A1_A1") (pintype "bidirectional"))
      (node (ref "J2") (pin "A12") (pinfunction "A12_A12") (pintype "bidirectional"))
      (node (ref "J2") (pin "B1") (pinfunction "B1_B1") (pintype "bidirectional"))
      (node (ref "J2") (pin "B12") (pinfunction "B12_B12") (pintype "bidirectional"))
      (node (ref "J2") (pin "MP1") (pinfunction "MP1_MP1") (pintype "bidirectional"))
      (node (ref "J2") (pin "MP2") (pinfunction "MP2_MP2") (pintype "bidirectional"))
      (node (ref "J2") (pin "MP3") (pinfunction "MP3_MP3") (pintype "bidirectional"))
      (node (ref "J2") (pin "MP4") (pinfunction "MP4_MP4") (pintype "bidirectional"))
      (node (ref "J3") (pin "1") (pinfunction "1_1") (pintype "power_in"))
      (node (ref "J4") (pin "G1") (pinfunction "GND_1_G1") (pintype "bidirectional"))
      (node (ref "J4") (pin "G2") (pinfunction "GND_2_G2") (pintype "bidirectional"))
      (node (ref "J4") (pin "G3") (pinfunction "GND_3_G3") (pintype "bidirectional"))
      (node (ref "J4") (pin "G4") (pinfunction "GND_4_G4") (pintype "bidirectional"))
      (node (ref "J4") (pin "P6") (pinfunction "VSS_P6") (pintype "bidirectional"))
      (node (ref "MCP73831") (pin "2") (pinfunction "VSS_2") (pintype "power_in"))
      (node (ref "R1_PWRUSB") (pin "1") (pinfunction "1_1") (pintype "passive"))
      (node (ref "R2") (pin "1") (pinfunction "1_1") (pintype "passive"))
      (node (ref "R2-USB") (pin "2") (pinfunction "2_2") (pintype "passive"))
      (node (ref "R2-USB1") (pin "1") (pinfunction "1_1") (pintype "passive"))
      (node (ref "R2_BAT") (pin "1") (pinfunction "1_1") (pintype "passive"))
      (node (ref "R4") (pin "2") (pinfunction "2_2") (pintype "passive"))
      (node (ref "RESET_BUTTON") (pin "1") (pinfunction "1_1") (pintype "passive"))
      (node (ref "RESET_BUTTON") (pin "2") (pinfunction "2_2") (pintype "passive"))
      (node (ref "SENSOR2") (pin "1") (pinfunction "GND_1") (pintype "power_in"))
      (node (ref "SENSOR2") (pin "5") (pinfunction "SDO_5") (pintype "bidirectional"))
      (node (ref "SENSOR2") (pin "7") (pinfunction "GND_7") (pintype "power_in"))
      (node (ref "SJ1") (pin "1") (pinfunction "1_1") (pintype "passive"))
      (node (ref "TP4") (pin "TP") (pinfunction "TP_TP") (pintype "input"))
      (node (ref "TP5") (pin "TP") (pinfunction "TP_TP") (pintype "input"))
      (node (ref "U1") (pin "4") (pinfunction "GND_4") (pintype "power_in"))
      (node (ref "U1") (pin "9") (pinfunction "EXP_9") (pintype "passive"))
      (node (ref "U2") (pin "1") (pinfunction "GND_1") (pintype "power_in"))
      (node (ref "U2") (pin "28") (pinfunction "GND_28") (pintype "power_in"))
      (node (ref "U2") (pin "29_1") (pinfunction "GND_29_1") (pintype "power_in"))
      (node (ref "U2") (pin "29_2") (pinfunction "GND_29_2") (pintype "power_in"))
      (node (ref "U2") (pin "29_3") (pinfunction "GND_29_3") (pintype "power_in"))
      (node (ref "U2") (pin "29_4") (pinfunction "GND_29_4") (pintype "power_in"))
      (node (ref "U2") (pin "29_5") (pinfunction "GND_29_5") (pintype "power_in"))
      (node (ref "U2") (pin "29_6") (pinfunction "GND_29_6") (pintype "power_in"))
      (node (ref "U2") (pin "29_7") (pinfunction "GND_29_7") (pintype "power_in"))
      (node (ref "U2") (pin "29_8") (pinfunction "GND_29_8") (pintype "power_in"))
      (node (ref "U2") (pin "29_9") (pinfunction "GND_29_9") (pintype "power_in"))
      (node (ref "U3") (pin "13") (pinfunction "GND_13") (pintype "power_in"))
      (node (ref "U4") (pin "1") (pinfunction "CTG_1") (pintype "power_in"))
      (node (ref "U4") (pin "4") (pinfunction "GND_4") (pintype "power_in"))
      (node (ref "U4") (pin "6") (pinfunction "QSTRT_6") (pintype "input"))
      (node (ref "U4") (pin "9") (pinfunction "EP_9") (pintype "power_in"))
    )
    (net (code "14") (name "GPIO8") (class "Default")
      (node (ref "R1") (pin "2") (pinfunction "2_2") (pintype "passive"))
      (node (ref "U2") (pin "10") (pinfunction "IO8_10") (pintype "bidirectional"))
    )
    (net (code "15") (name "I2C_PW") (class "Default")
      (node (ref "C1") (pin "1") (pinfunction "1_1") (pintype "passive"))
      (node (ref "C2") (pin "1") (pinfunction "1_1") (pintype "passive"))
      (node (ref "R1_PINH") (pin "2") (pinfunction "2_2") (pintype "passive"))
      (node (ref "R2-PINH") (pin "2") (pinfunction "2_2") (pintype "passive"))
      (node (ref "SENSOR2") (pin "2") (pinfunction "CSB_2") (pintype "input"))
      (node (ref "SENSOR2") (pin "6") (pinfunction "VDDIO_6") (pintype "power_in"))
      (node (ref "SENSOR2") (pin "8") (pinfunction "VDD_8") (pintype "power_in"))
      (node (ref "U2") (pin "17") (pinfunction "IO19_17") (pintype "bidirectional"))
    )
    (net (code "16") (name "INT_RTC") (class "Default")
      (node (ref "R1_PINH1") (pin "1") (pinfunction "1_1") (pintype "passive"))
      (node (ref "TP15") (pin "TP") (pinfunction "TP_TP") (pintype "input"))
      (node (ref "U2") (pin "8") (pinfunction "IO0_8") (pintype "bidirectional"))
      (node (ref "U3") (pin "3") (pinfunction "SQW/~{INT}_3") (pintype "output"))
    )
    (net (code "17") (name "IO{slash}BOOT") (class "Default")
      (node (ref "BOOT_BUTTON") (pin "3") (pinfunction "3_3") (pintype "passive"))
      (node (ref "BOOT_BUTTON") (pin "4") (pinfunction "4_4") (pintype "passive"))
      (node (ref "C6") (pin "1") (pinfunction "1_1") (pintype "passive"))
      (node (ref "R_BOOT") (pin "2") (pinfunction "2_2") (pintype "passive"))
      (node (ref "U2") (pin "15") (pinfunction "IO9_15") (pintype "bidirectional"))
    )
    (net (code "18") (name "IO{slash}CHANGE") (class "Default")
      (node (ref "C10") (pin "1") (pinfunction "1_1") (pintype "passive"))
      (node (ref "CHANGE_BUTTON") (pin "3") (pinfunction "3_3") (pintype "passive"))
      (node (ref "CHANGE_BUTTON") (pin "4") (pinfunction "4_4") (pintype "passive"))
      (node (ref "R_CHANGE") (pin "2") (pinfunction "2_2") (pintype "passive"))
      (node (ref "U2") (pin "23") (pinfunction "IO15_23") (pintype "bidirectional"))
    )
    (net (code "19") (name "MISO") (class "Default")
      (node (ref "D12") (pin "1") (pinfunction "1_1") (pintype "passive"))
      (node (ref "J4") (pin "P7") (pinfunction "DAT0_P7") (pintype "bidirectional"))
      (node (ref "R8") (pin "1") (pinfunction "1_1") (pintype "passive"))
      (node (ref "TP6") (pin "TP") (pinfunction "TP_TP") (pintype "input"))
      (node (ref "U1") (pin "2") (pinfunction "DO(IO1)_2") (pintype "bidirectional"))
      (node (ref "U2") (pin "27") (pinfunction "IO2_27") (pintype "bidirectional"))
    )
    (net (code "20") (name "MOSI") (class "Default")
      (node (ref "D11") (pin "1") (pinfunction "1_1") (pintype "passive"))
      (node (ref "J1") (pin "14") (pinfunction "14_14") (pintype "bidirectional"))
      (node (ref "J4") (pin "P3") (pinfunction "CMD_P3") (pintype "bidirectional"))
      (node (ref "R7") (pin "1") (pinfunction "1_1") (pintype "passive"))
      (node (ref "TP7") (pin "TP") (pinfunction "TP_TP") (pintype "input"))
      (node (ref "U1") (pin "5") (pinfunction "DI(IO0)_5") (pintype "bidirectional"))
      (node (ref "U2") (pin "7") (pinfunction "IO7_7") (pintype "bidirectional"))
    )
    (net (code "21") (name "Net-(CHG_LED-PadC)") (class "Default")
      (node (ref "CHG_LED") (pin "C") (pinfunction "C_C") (pintype "passive"))
      (node (ref "R1_BAT") (pin "2") (pinfunction "2_2") (pintype "passive"))
    )
    (net (code "22") (name "Net-(D2-CATHODE)") (class "Default")
      (node (ref "C1_BAT1") (pin "1") (pinfunction "1_1") (pintype "passive"))
      (node (ref "D2") (pin "1") (pinfunction "CATHODE_1") (pintype "bidirectional"))
      (node (ref "IC4") (pin "1") (pinfunction "VIN_1") (pintype "bidirectional"))
      (node (ref "IC4") (pin "3") (pinfunction "CE_3") (pintype "bidirectional"))
      (node (ref "Q1") (pin "2") (pinfunction "S_2") (pintype "bidirectional"))
    )
    (net (code "23") (name "Net-(D3-A)") (class "Default")
      (node (ref "C4") (pin "1") (pinfunction "1_1") (pintype "passive"))
      (node (ref "D3") (pin "2") (pinfunction "A_2") (pintype "bidirectional"))
      (node (ref "D4") (pin "1") (pinfunction "K_1") (pintype "bidirectional"))
    )
    (net (code "24") (name "Net-(D7-CATHODE)") (class "Default")
      (node (ref "D7") (pin "1") (pinfunction "CATHODE_1") (pintype "bidirectional"))
      (node (ref "R_CAPACITOR") (pin "1") (pinfunction "1_1") (pintype "passive"))
    )
    (net (code "25") (name "Net-(EPD_C1-Pad1)") (class "Default")
      (node (ref "EPD_C1") (pin "1") (pinfunction "1_1") (pintype "passive"))
      (node (ref "J1") (pin "4") (pinfunction "4_4") (pintype "bidirectional"))
    )
    (net (code "26") (name "Net-(EPD_C2-Pad1)") (class "Default")
      (node (ref "EPD_C2") (pin "1") (pinfunction "1_1") (pintype "passive"))
      (node (ref "J1") (pin "5") (pinfunction "5_5") (pintype "bidirectional"))
    )
    (net (code "27") (name "Net-(EPD_C6-Pad1)") (class "Default")
      (node (ref "EPD_C6") (pin "1") (pinfunction "1_1") (pintype "passive"))
      (node (ref "J1") (pin "18") (pinfunction "18_18") (pintype "bidirectional"))
    )
    (net (code "28") (name "Net-(EPD_C7-Pad1)") (class "Default")
      (node (ref "EPD_C7") (pin "1") (pinfunction "1_1") (pintype "passive"))
      (node (ref "J1") (pin "19") (pinfunction "19_19") (pintype "bidirectional"))
    )
    (net (code "29") (name "Net-(EPD_C8-Pad1)") (class "Default")
      (node (ref "EPD_C8") (pin "1") (pinfunction "1_1") (pintype "passive"))
      (node (ref "J1") (pin "20") (pinfunction "20_20") (pintype "bidirectional"))
    )
    (net (code "30") (name "Net-(EPD_C10-Pad1)") (class "Default")
      (node (ref "EPD_C10") (pin "1") (pinfunction "1_1") (pintype "passive"))
      (node (ref "J1") (pin "22") (pinfunction "22_22") (pintype "bidirectional"))
    )
    (net (code "31") (name "Net-(EPD_C12-Pad1)") (class "Default")
      (node (ref "EPD_C12") (pin "1") (pinfunction "1_1") (pintype "passive"))
      (node (ref "J1") (pin "24") (pinfunction "24_24") (pintype "bidirectional"))
    )
    (net (code "32") (name "Net-(IC1-CT)") (class "Default")
      (node (ref "C_DELAY") (pin "1") (pinfunction "1_1") (pintype "passive"))
      (node (ref "IC1") (pin "5") (pinfunction "CT_5") (pintype "bidirectional"))
    )
    (net (code "33") (name "Net-(J2-PadA5)") (class "Default")
      (node (ref "J2") (pin "A5") (pinfunction "A5_A5") (pintype "bidirectional"))
      (node (ref "R2-USB1") (pin "2") (pinfunction "2_2") (pintype "passive"))
    )
    (net (code "34") (name "Net-(J2-PadB5)") (class "Default")
      (node (ref "J2") (pin "B5") (pinfunction "B5_B5") (pintype "bidirectional"))
      (node (ref "R2-USB") (pin "1") (pinfunction "1_1") (pintype "passive"))
    )
    (net (code "35") (name "Net-(MCP73831-PROG)") (class "Default")
      (node (ref "MCP73831") (pin "5") (pinfunction "PROG_5") (pintype "input"))
      (node (ref "R2_BAT") (pin "2") (pinfunction "2_2") (pintype "passive"))
    )
    (net (code "36") (name "Net-(MCP73831-STAT)") (class "Default")
      (node (ref "MCP73831") (pin "1") (pinfunction "STAT_1") (pintype "output"))
      (node (ref "R1_BAT") (pin "1") (pinfunction "1_1") (pintype "passive"))
    )
    (net (code "37") (name "PREVGH") (class "Default")
      (node (ref "D5") (pin "1") (pinfunction "K_1") (pintype "bidirectional"))
      (node (ref "EPD_C9") (pin "1") (pinfunction "1_1") (pintype "passive"))
      (node (ref "J1") (pin "21") (pinfunction "21_21") (pintype "bidirectional"))
    )
    (net (code "38") (name "PREVGL") (class "Default")
      (node (ref "D4") (pin "2") (pinfunction "A_2") (pintype "bidirectional"))
      (node (ref "EPD_C11") (pin "1") (pinfunction "1_1") (pintype "passive"))
      (node (ref "J1") (pin "23") (pinfunction "23_23") (pintype "bidirectional"))
    )
    (net (code "39") (name "RESE") (class "Default")
      (node (ref "J1") (pin "3") (pinfunction "3_3") (pintype "bidirectional"))
      (node (ref "Q3") (pin "2") (pinfunction "S_2") (pintype "bidirectional"))
      (node (ref "R3") (pin "1") (pinfunction "1_1") (pintype "passive"))
    )
    (net (code "40") (name "RESE'") (class "Default")
      (node (ref "R2") (pin "2") (pinfunction "2_2") (pintype "passive"))
      (node (ref "R3") (pin "2") (pinfunction "2_2") (pintype "passive"))
      (node (ref "SJ1") (pin "2") (pinfunction "2_2") (pintype "passive"))
    )
    (net (code "41") (name "RESET") (class "Default")
      (node (ref "C5") (pin "1") (pinfunction "1_1") (pintype "passive"))
      (node (ref "IC1") (pin "1") (pinfunction "VOUT_1") (pintype "bidirectional"))
      (node (ref "RESET_BUTTON") (pin "3") (pinfunction "3_3") (pintype "passive"))
      (node (ref "RESET_BUTTON") (pin "4") (pinfunction "4_4") (pintype "passive"))
      (node (ref "R_RESET") (pin "2") (pinfunction "2_2") (pintype "passive"))
      (node (ref "U2") (pin "3") (pinfunction "EN_3") (pintype "input"))
    )
    (net (code "42") (name "RTC_RST") (class "Default")
      (node (ref "U2") (pin "16") (pinfunction "IO18_16") (pintype "bidirectional"))
      (node (ref "U3") (pin "4") (pinfunction "~{RST}_4") (pintype "input"))
    )
    (net (code "43") (name "RX") (class "Default")
      (node (ref "TP2") (pin "TP") (pinfunction "TP_TP") (pintype "input"))
      (node (ref "U2") (pin "24") (pinfunction "RXD0/GPIO17_24") (pintype "bidirectional"))
    )
    (net (code "44") (name "SCK") (class "Default")
      (node (ref "D10") (pin "1") (pinfunction "1_1") (pintype "passive"))
      (node (ref "J1") (pin "13") (pinfunction "13_13") (pintype "bidirectional"))
      (node (ref "J4") (pin "P5") (pinfunction "CLK_P5") (pintype "bidirectional"))
      (node (ref "R6") (pin "1") (pinfunction "1_1") (pintype "passive"))
      (node (ref "TP8") (pin "TP") (pinfunction "TP_TP") (pintype "input"))
      (node (ref "U1") (pin "6") (pinfunction "CLK_6") (pintype "input"))
      (node (ref "U2") (pin "6") (pinfunction "IO6_6") (pintype "bidirectional"))
    )
    (net (code "45") (name "SCL") (class "Default")
      (node (ref "J3") (pin "4") (pinfunction "4_4") (pintype "passive"))
      (node (ref "R2-PINH") (pin "1") (pinfunction "1_1") (pintype "passive"))
      (node (ref "SENSOR2") (pin "4") (pinfunction "SCK_4") (pintype "input"))
      (node (ref "U2") (pin "20") (pinfunction "IO22_20") (pintype "bidirectional"))
      (node (ref "U3") (pin "16") (pinfunction "SCL_16") (pintype "input"))
      (node (ref "U4") (pin "7") (pinfunction "SCL_7") (pintype "input"))
    )
    (net (code "46") (name "SDA") (class "Default")
      (node (ref "J3") (pin "3") (pinfunction "3_3") (pintype "passive"))
      (node (ref "R1_PINH") (pin "1") (pinfunction "1_1") (pintype "passive"))
      (node (ref "SENSOR2") (pin "3") (pinfunction "SDI_3") (pintype "bidirectional"))
      (node (ref "U2") (pin "19") (pinfunction "IO21_19") (pintype "bidirectional"))
      (node (ref "U3") (pin "15") (pinfunction "SDA_15") (pintype "bidirectional"))
      (node (ref "U4") (pin "8") (pinfunction "SDA_8") (pintype "bidirectional"))
    )
    (net (code "47") (name "SRC") (class "Default")
      (node (ref "C4") (pin "2") (pinfunction "2_2") (pintype "passive"))
      (node (ref "D5") (pin "2") (pinfunction "A_2") (pintype "bidirectional"))
      (node (ref "L1") (pin "1") (pinfunction "1_1") (pintype "passive"))
      (node (ref "Q3") (pin "3") (pinfunction "D_3") (pintype "bidirectional"))
    )
    (net (code "48") (name "SS_SD") (class "Default")
      (node (ref "D8") (pin "1") (pinfunction "1_1") (pintype "passive"))
      (node (ref "J4") (pin "P2") (pinfunction "CD/DAT3_P2") (pintype "bidirectional"))
      (node (ref "R10") (pin "1") (pinfunction "1_1") (pintype "passive"))
      (node (ref "U2") (pin "4") (pinfunction "IO4_4") (pintype "bidirectional"))
    )
    (net (code "49") (name "TX") (class "Default")
      (node (ref "TP1") (pin "TP") (pinfunction "TP_TP") (pintype "input"))
      (node (ref "U2") (pin "25") (pinfunction "TXD0/GPIO16_25") (pintype "bidirectional"))
    )
    (net (code "50") (name "USB_D+") (class "Default")
      (node (ref "D1") (pin "1") (pinfunction "I/O1_1_1") (pintype "bidirectional"))
      (node (ref "U2") (pin "14") (pinfunction "IO13_14") (pintype "bidirectional"))
    )
    (net (code "51") (name "USB_D-") (class "Default")
      (node (ref "D1") (pin "3") (pinfunction "I/O2_1_3") (pintype "bidirectional"))
      (node (ref "U2") (pin "13") (pinfunction "IO12_13") (pintype "bidirectional"))
    )
    (net (code "52") (name "VBAT") (class "Default")
      (node (ref "C2_BAT") (pin "1") (pinfunction "1_1") (pintype "passive"))
      (node (ref "MCP73831") (pin "3") (pinfunction "VBAT_3") (pintype "power_in"))
      (node (ref "Q1") (pin "3") (pinfunction "D_3") (pintype "bidirectional"))
      (node (ref "TP3") (pin "TP") (pinfunction "TP_TP") (pintype "input"))
      (node (ref "U4") (pin "2") (pinfunction "CELL_2") (pintype "power_in"))
      (node (ref "U4") (pin "3") (pinfunction "VDD_3") (pintype "power_in"))
    )
    (net (code "53") (name "VBUS") (class "Default")
      (node (ref "C1_BAT") (pin "1") (pinfunction "1_1") (pintype "passive"))
      (node (ref "C4_USB") (pin "1") (pinfunction "1_1") (pintype "passive"))
      (node (ref "C5_USB") (pin "1") (pinfunction "1_1") (pintype "passive"))
      (node (ref "CHG_LED") (pin "A") (pinfunction "A_A") (pintype "passive"))
      (node (ref "D1") (pin "5") (pinfunction "VBUS_5") (pintype "bidirectional"))
      (node (ref "D2") (pin "2") (pinfunction "ANODE_2") (pintype "bidirectional"))
      (node (ref "MCP73831") (pin "4") (pinfunction "VIN_4") (pintype "power_in"))
      (node (ref "PFMF.050.1") (pin "2") (pinfunction "2_2") (pintype "passive"))
      (node (ref "Q1") (pin "1") (pinfunction "G_1") (pintype "bidirectional"))
      (node (ref "R1_PWRUSB") (pin "2") (pinfunction "2_2") (pintype "passive"))
      (node (ref "TP14") (pin "TP") (pinfunction "TP_TP") (pintype "input"))
    )
    (net (code "54") (name "VRTC") (class "Default")
      (node (ref "C10_SUPERCAP") (pin "2") (pinfunction "2_2") (pintype "passive"))
      (node (ref "C8") (pin "1") (pinfunction "1_1") (pintype "passive"))
      (node (ref "R_CAPACITOR") (pin "2") (pinfunction "2_2") (pintype "passive"))
      (node (ref "U3") (pin "14") (pinfunction "VBAT_14") (pintype "power_in"))
    )
    (net (code "55") (name "VUSB") (class "Default")
      (node (ref "J2") (pin "A4") (pinfunction "A4_A4") (pintype "bidirectional"))
      (node (ref "J2") (pin "A9") (pinfunction "A9_A9") (pintype "bidirectional"))
      (node (ref "J2") (pin "B4") (pinfunction "B4_B4") (pintype "bidirectional"))
      (node (ref "J2") (pin "B9") (pinfunction "B9_B9") (pintype "bidirectional"))
      (node (ref "PFMF.050.1") (pin "1") (pinfunction "1_1") (pintype "passive"))
    )
    (net (code "56") (name "unconnected-(IC1-NC-Pad4)") (class "Default")
      (node (ref "IC1") (pin "4") (pinfunction "NC_4") (pintype "no_connect"))
    )
    (net (code "57") (name "unconnected-(IC4-NC-Pad4)") (class "Default")
      (node (ref "IC4") (pin "4") (pinfunction "NC_4") (pintype "no_connect"))
    )
    (net (code "58") (name "unconnected-(J1-Pad1)") (class "Default")
      (node (ref "J1") (pin "1") (pinfunction "1_1") (pintype "bidirectional"))
    )
    (net (code "59") (name "unconnected-(J1-Pad6)") (class "Default")
      (node (ref "J1") (pin "6") (pinfunction "6_6") (pintype "bidirectional"))
    )
    (net (code "60") (name "unconnected-(J1-Pad7)") (class "Default")
      (node (ref "J1") (pin "7") (pinfunction "7_7") (pintype "bidirectional"))
    )
    (net (code "61") (name "unconnected-(J2-PadA8)") (class "Default")
      (node (ref "J2") (pin "A8") (pinfunction "A8_A8") (pintype "bidirectional"))
    )
    (net (code "62") (name "unconnected-(J2-PadB8)") (class "Default")
      (node (ref "J2") (pin "B8") (pinfunction "B8_B8") (pintype "bidirectional"))
    )
    (net (code "63") (name "unconnected-(J4-DAT1-PadP8)") (class "Default")
      (node (ref "J4") (pin "P8") (pinfunction "DAT1_P8") (pintype "bidirectional"))
    )
    (net (code "64") (name "unconnected-(J4-DAT2-PadP1)") (class "Default")
      (node (ref "J4") (pin "P1") (pinfunction "DAT2_P1") (pintype "bidirectional"))
    )
    (net (code "65") (name "unconnected-(J4-DETECTION_1-PadS1)") (class "Default")
      (node (ref "J4") (pin "S1") (pinfunction "DETECTION_1_S1") (pintype "bidirectional"))
    )
    (net (code "66") (name "unconnected-(J4-DETECTION_2-PadS2)") (class "Default")
      (node (ref "J4") (pin "S2") (pinfunction "DETECTION_2_S2") (pintype "bidirectional"))
    )
    (net (code "67") (name "unconnected-(U2-NC-Pad22)") (class "Default")
      (node (ref "U2") (pin "22") (pinfunction "NC_22") (pintype "no_connect"))
    )
    (net (code "68") (name "unconnected-(U4-~{ALERT}-Pad5)") (class "Default")
      (node (ref "U4") (pin "5") (pinfunction "~{ALERT}_5") (pintype "output"))
    )
  )
)
